# PCB_board.net
KiCad netlist of a schematic drawn in EAGLE
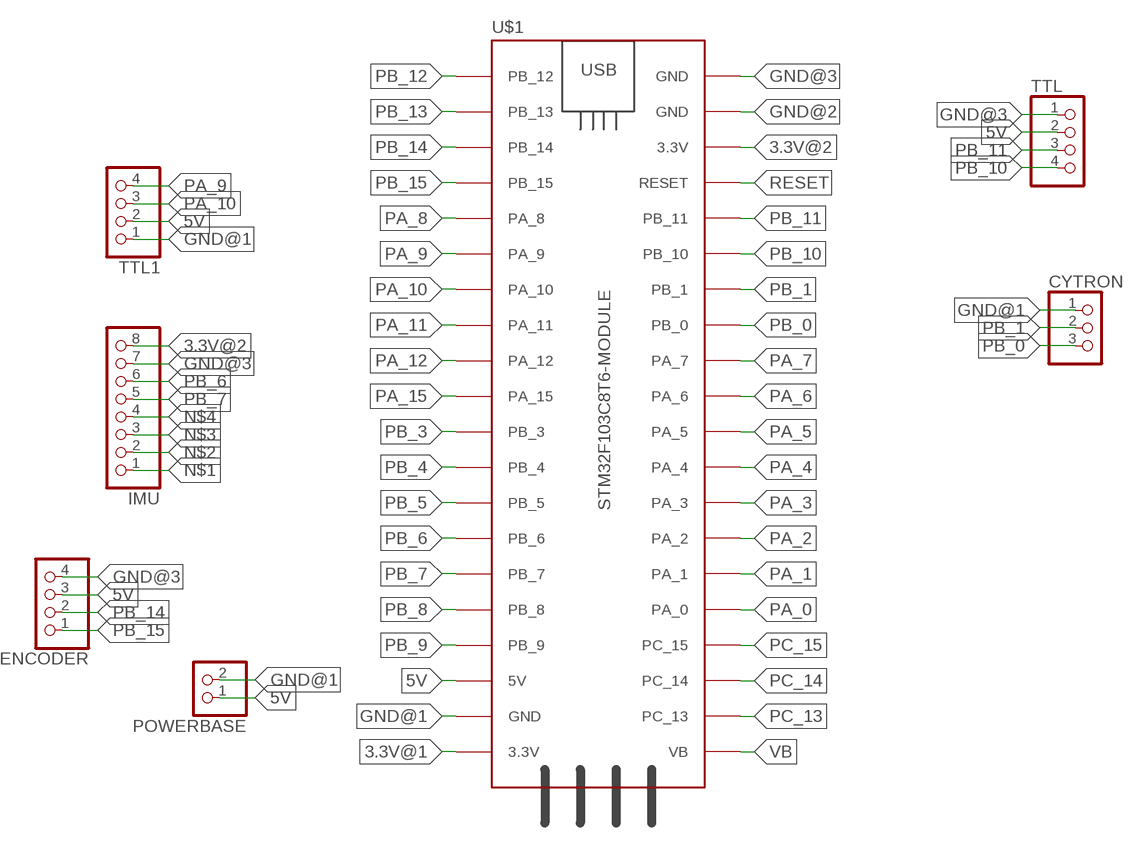
[diagram p0: schematic, sheet 1]

(export (version "E")
  (design (tool "Eeschema 10.0.6"))
  (components
    (comp (ref "CYTRON")
      (value "PINHD-1X3")
      (footprint "eagle-import:1X03")
      (libsource (lib "eagle-import") (part "PINHD-1X3"))
    )
    (comp (ref "ENCODER")
      (value "PINHD-4_DATA")
      (footprint "eagle-import:1X04_DATA")
      (libsource (lib "eagle-import") (part "PINHD-4_DATA"))
    )
    (comp (ref "IMU")
      (value "PINHD-1X8")
      (footprint "eagle-import:1X08")
      (libsource (lib "eagle-import") (part "PINHD-1X8"))
    )
    (comp (ref "POWERBASE")
      (value "PINHD-1X2")
      (footprint "eagle-import:1X02")
      (libsource (lib "eagle-import") (part "PINHD-1X2"))
    )
    (comp (ref "TTL")
      (value "PINHD-4_DATA")
      (footprint "eagle-import:1X04_DATA")
      (libsource (lib "eagle-import") (part "PINHD-4_DATA"))
    )
    (comp (ref "TTL1")
      (value "PINHD-4_DATA")
      (footprint "eagle-import:1X04_DATA")
      (libsource (lib "eagle-import") (part "PINHD-4_DATA"))
    )
    (comp (ref "U$1")
      (value "STM32F103C8T6-MODULE")
      (footprint "eagle-import:STM32F103C8T6-MODULE")
      (libsource (lib "eagle-import") (part "STM32F103C8T6-MODULE"))
    )
  )
  (nets
    (net (code "1") (name "3.3V@1") (class "Default")
      (node (ref "U$1") (pin "3.3V_1") (pinfunction "3.3V_3.3V_1") (pintype "bidirectional"))
    )
    (net (code "2") (name "3.3V@2") (class "Default")
      (node (ref "IMU") (pin "8") (pinfunction "8_8") (pintype "passive"))
      (node (ref "U$1") (pin "3.3V_2") (pinfunction "3.3V_3.3V_2") (pintype "bidirectional"))
    )
    (net (code "3") (name "5V") (class "Default")
      (node (ref "ENCODER") (pin "3") (pinfunction "3_3") (pintype "passive"))
      (node (ref "POWERBASE") (pin "1") (pinfunction "1_1") (pintype "passive"))
      (node (ref "TTL") (pin "2") (pinfunction "2_2") (pintype "passive"))
      (node (ref "TTL1") (pin "2") (pinfunction "2_2") (pintype "passive"))
      (node (ref "U$1") (pin "5V") (pinfunction "5V_5V") (pintype "bidirectional"))
    )
    (net (code "4") (name "GND@1") (class "Default")
      (node (ref "CYTRON") (pin "1") (pinfunction "1_1") (pintype "passive"))
      (node (ref "POWERBASE") (pin "2") (pinfunction "2_2") (pintype "passive"))
      (node (ref "TTL1") (pin "1") (pinfunction "1_1") (pintype "passive"))
      (node (ref "U$1") (pin "GND_1") (pinfunction "GND_GND_1") (pintype "bidirectional"))
    )
    (net (code "5") (name "GND@2") (class "Default")
      (node (ref "U$1") (pin "GND_2") (pinfunction "GND_GND_2") (pintype "bidirectional"))
    )
    (net (code "6") (name "GND@3") (class "Default")
      (node (ref "ENCODER") (pin "4") (pinfunction "4_4") (pintype "passive"))
      (node (ref "IMU") (pin "7") (pinfunction "7_7") (pintype "passive"))
      (node (ref "TTL") (pin "1") (pinfunction "1_1") (pintype "passive"))
      (node (ref "U$1") (pin "GND_3") (pinfunction "GND_GND_3") (pintype "power_in"))
    )
    (net (code "7") (name "N$1") (class "Default")
      (node (ref "IMU") (pin "1") (pinfunction "1_1") (pintype "passive"))
    )
    (net (code "8") (name "N$2") (class "Default")
      (node (ref "IMU") (pin "2") (pinfunction "2_2") (pintype "passive"))
    )
    (net (code "9") (name "N$3") (class "Default")
      (node (ref "IMU") (pin "3") (pinfunction "3_3") (pintype "passive"))
    )
    (net (code "10") (name "N$4") (class "Default")
      (node (ref "IMU") (pin "4") (pinfunction "4_4") (pintype "passive"))
    )
    (net (code "11") (name "PA_0") (class "Default")
      (node (ref "U$1") (pin "PA_0") (pinfunction "PA_0_PA_0") (pintype "bidirectional"))
    )
    (net (code "12") (name "PA_1") (class "Default")
      (node (ref "U$1") (pin "PA_1") (pinfunction "PA_1_PA_1") (pintype "bidirectional"))
    )
    (net (code "13") (name "PA_2") (class "Default")
      (node (ref "U$1") (pin "PA_2") (pinfunction "PA_2_PA_2") (pintype "bidirectional"))
    )
    (net (code "14") (name "PA_3") (class "Default")
      (node (ref "U$1") (pin "PA_3") (pinfunction "PA_3_PA_3") (pintype "bidirectional"))
    )
    (net (code "15") (name "PA_4") (class "Default")
      (node (ref "U$1") (pin "PA_4") (pinfunction "PA_4_PA_4") (pintype "bidirectional"))
    )
    (net (code "16") (name "PA_5") (class "Default")
      (node (ref "U$1") (pin "PA_5") (pinfunction "PA_5_PA_5") (pintype "bidirectional"))
    )
    (net (code "17") (name "PA_6") (class "Default")
      (node (ref "U$1") (pin "PA_6") (pinfunction "PA_6_PA_6") (pintype "bidirectional"))
    )
    (net (code "18") (name "PA_7") (class "Default")
      (node (ref "U$1") (pin "PA_7") (pinfunction "PA_7_PA_7") (pintype "bidirectional"))
    )
    (net (code "19") (name "PA_8") (class "Default")
      (node (ref "U$1") (pin "PA_8") (pinfunction "PA_8_PA_8") (pintype "bidirectional"))
    )
    (net (code "20") (name "PA_9") (class "Default")
      (node (ref "TTL1") (pin "4") (pinfunction "4_4") (pintype "passive"))
      (node (ref "U$1") (pin "PA_9") (pinfunction "PA_9_PA_9") (pintype "bidirectional"))
    )
    (net (code "21") (name "PA_10") (class "Default")
      (node (ref "TTL1") (pin "3") (pinfunction "3_3") (pintype "passive"))
      (node (ref "U$1") (pin "PA_10") (pinfunction "PA_10_PA_10") (pintype "bidirectional"))
    )
    (net (code "22") (name "PA_11") (class "Default")
      (node (ref "U$1") (pin "PA_11") (pinfunction "PA_11_PA_11") (pintype "bidirectional"))
    )
    (net (code "23") (name "PA_12") (class "Default")
      (node (ref "U$1") (pin "PA_12") (pinfunction "PA_12_PA_12") (pintype "bidirectional"))
    )
    (net (code "24") (name "PA_15") (class "Default")
      (node (ref "U$1") (pin "PA_15") (pinfunction "PA_15_PA_15") (pintype "bidirectional"))
    )
    (net (code "25") (name "PB_0") (class "Default")
      (node (ref "CYTRON") (pin "3") (pinfunction "3_3") (pintype "passive"))
      (node (ref "U$1") (pin "PB_0") (pinfunction "PB_0_PB_0") (pintype "bidirectional"))
    )
    (net (code "26") (name "PB_1") (class "Default")
      (node (ref "CYTRON") (pin "2") (pinfunction "2_2") (pintype "passive"))
      (node (ref "U$1") (pin "PB_1") (pinfunction "PB_1_PB_1") (pintype "bidirectional"))
    )
    (net (code "27") (name "PB_3") (class "Default")
      (node (ref "U$1") (pin "PB_3") (pinfunction "PB_3_PB_3") (pintype "bidirectional"))
    )
    (net (code "28") (name "PB_4") (class "Default")
      (node (ref "U$1") (pin "PB_4") (pinfunction "PB_4_PB_4") (pintype "bidirectional"))
    )
    (net (code "29") (name "PB_5") (class "Default")
      (node (ref "U$1") (pin "PB_5") (pinfunction "PB_5_PB_5") (pintype "bidirectional"))
    )
    (net (code "30") (name "PB_6") (class "Default")
      (node (ref "IMU") (pin "6") (pinfunction "6_6") (pintype "passive"))
      (node (ref "U$1") (pin "PB_6") (pinfunction "PB_6_PB_6") (pintype "bidirectional"))
    )
    (net (code "31") (name "PB_7") (class "Default")
      (node (ref "IMU") (pin "5") (pinfunction "5_5") (pintype "passive"))
      (node (ref "U$1") (pin "PB_7") (pinfunction "PB_7_PB_7") (pintype "bidirectional"))
    )
    (net (code "32") (name "PB_8") (class "Default")
      (node (ref "U$1") (pin "PB_8") (pinfunction "PB_8_PB_8") (pintype "bidirectional"))
    )
    (net (code "33") (name "PB_9") (class "Default")
      (node (ref "U$1") (pin "PB_9") (pinfunction "PB_9_PB_9") (pintype "bidirectional"))
    )
    (net (code "34") (name "PB_10") (class "Default")
      (node (ref "TTL") (pin "4") (pinfunction "4_4") (pintype "passive"))
      (node (ref "U$1") (pin "PB_10") (pinfunction "PB_10_PB_10") (pintype "bidirectional"))
    )
    (net (code "35") (name "PB_11") (class "Default")
      (node (ref "TTL") (pin "3") (pinfunction "3_3") (pintype "passive"))
      (node (ref "U$1") (pin "PB_11") (pinfunction "PB_11_PB_11") (pintype "bidirectional"))
    )
    (net (code "36") (name "PB_12") (class "Default")
      (node (ref "U$1") (pin "PB_12") (pinfunction "PB_12_PB_12") (pintype "bidirectional"))
    )
    (net (code "37") (name "PB_13") (class "Default")
      (node (ref "U$1") (pin "PB_13") (pinfunction "PB_13_PB_13") (pintype "bidirectional"))
    )
    (net (code "38") (name "PB_14") (class "Default")
      (node (ref "ENCODER") (pin "2") (pinfunction "2_2") (pintype "passive"))
      (node (ref "U$1") (pin "PB_14") (pinfunction "PB_14_PB_14") (pintype "bidirectional"))
    )
    (net (code "39") (name "PB_15") (class "Default")
      (node (ref "ENCODER") (pin "1") (pinfunction "1_1") (pintype "passive"))
      (node (ref "U$1") (pin "PB_15") (pinfunction "PB_15_PB_15") (pintype "bidirectional"))
    )
    (net (code "40") (name "PC_13") (class "Default")
      (node (ref "U$1") (pin "PC_13") (pinfunction "PC_13_PC_13") (pintype "bidirectional"))
    )
    (net (code "41") (name "PC_14") (class "Default")
      (node (ref "U$1") (pin "PC_14") (pinfunction "PC_14_PC_14") (pintype "bidirectional"))
    )
    (net (code "42") (name "PC_15") (class "Default")
      (node (ref "U$1") (pin "PC_15") (pinfunction "PC_15_PC_15") (pintype "bidirectional"))
    )
    (net (code "43") (name "RESET") (class "Default")
      (node (ref "U$1") (pin "RESET") (pinfunction "RESET_RESET") (pintype "bidirectional"))
    )
    (net (code "44") (name "VB") (class "Default")
      (node (ref "U$1") (pin "VB") (pinfunction "VB_VB") (pintype "bidirectional"))
    )
  )
)
